# IMU.net
KiCad netlist of a schematic drawn in Altium Designer
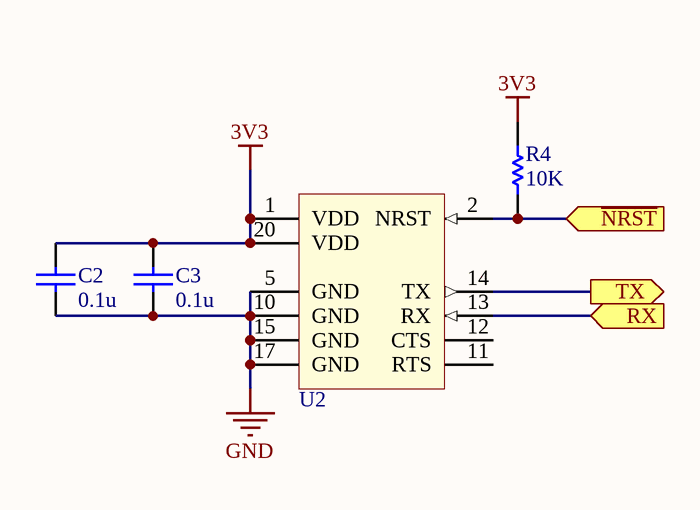
[diagram p0: IMU.SchDoc]

(export (version "E")
  (design (tool "Eeschema 10.0.6"))
  (components
    (comp (ref "C2")
      (value "0.1u")
      (footprint "CAPC1608X90N")
      (description "Capacitor")
      (fields (field (name "Comment") "Cap") (field (name "PUBLISHER") "Altium Limited"))
      (libsource (lib "IOBoard_Low") (part "Cap"))
    )
    (comp (ref "C3")
      (value "0.1u")
      (footprint "CAPC1608X90N")
      (description "Capacitor")
      (fields (field (name "Comment") "Cap") (field (name "PUBLISHER") "Altium Limited"))
      (libsource (lib "IOBoard_Low") (part "Cap"))
    )
    (comp (ref "R4")
      (value "10K")
      (footprint "RESC1608X55N")
      (description "Resistor")
      (fields (field (name "Comment") "Res1") (field (name "PUBLISHER") "Altium Limited"))
      (libsource (lib "IOBoard_Low") (part "Res1"))
    )
    (comp (ref "U2")
      (value "LPMS-NAV2")
      (footprint "LPMS-NAV2")
      (libsource (lib "IOBoard_Low") (part "LPMS-NAV2"))
    )
  )
  (nets
    (net (code "1") (name "/RX") (class "Default")
      (node (ref "U2") (pin "13") (pinfunction "RX_13") (pintype "input"))
    )
    (net (code "2") (name "/TX") (class "Default")
      (node (ref "U2") (pin "14") (pinfunction "TX_14") (pintype "output"))
    )
    (net (code "3") (name "/~{NRST}") (class "Default")
      (node (ref "R4") (pin "1") (pinfunction "1_1") (pintype "passive"))
      (node (ref "U2") (pin "2") (pinfunction "NRST_2") (pintype "input"))
    )
    (net (code "4") (name "3V3") (class "Default")
      (node (ref "C2") (pin "2") (pinfunction "2_2") (pintype "passive"))
      (node (ref "C3") (pin "2") (pinfunction "2_2") (pintype "passive"))
      (node (ref "R4") (pin "2") (pinfunction "2_2") (pintype "passive"))
      (node (ref "U2") (pin "1") (pinfunction "VDD_1") (pintype "power_in"))
      (node (ref "U2") (pin "20") (pinfunction "VDD_20") (pintype "power_in"))
    )
    (net (code "5") (name "GND") (class "Default")
      (node (ref "C2") (pin "1") (pinfunction "1_1") (pintype "passive"))
      (node (ref "C3") (pin "1") (pinfunction "1_1") (pintype "passive"))
      (node (ref "U2") (pin "10") (pinfunction "GND_10") (pintype "power_in"))
      (node (ref "U2") (pin "15") (pinfunction "GND_15") (pintype "power_in"))
      (node (ref "U2") (pin "17") (pinfunction "GND_17") (pintype "power_in"))
      (node (ref "U2") (pin "5") (pinfunction "GND_5") (pintype "power_in"))
    )
    (net (code "6") (name "unconnected-(U2-CTS-Pad12)") (class "Default")
      (node (ref "U2") (pin "12") (pinfunction "CTS_12") (pintype "passive"))
    )
    (net (code "7") (name "unconnected-(U2-RTS-Pad11)") (class "Default")
      (node (ref "U2") (pin "11") (pinfunction "RTS_11") (pintype "passive"))
    )
  )
)
